# Solar.net
KiCad netlist of a schematic drawn in Altium Designer
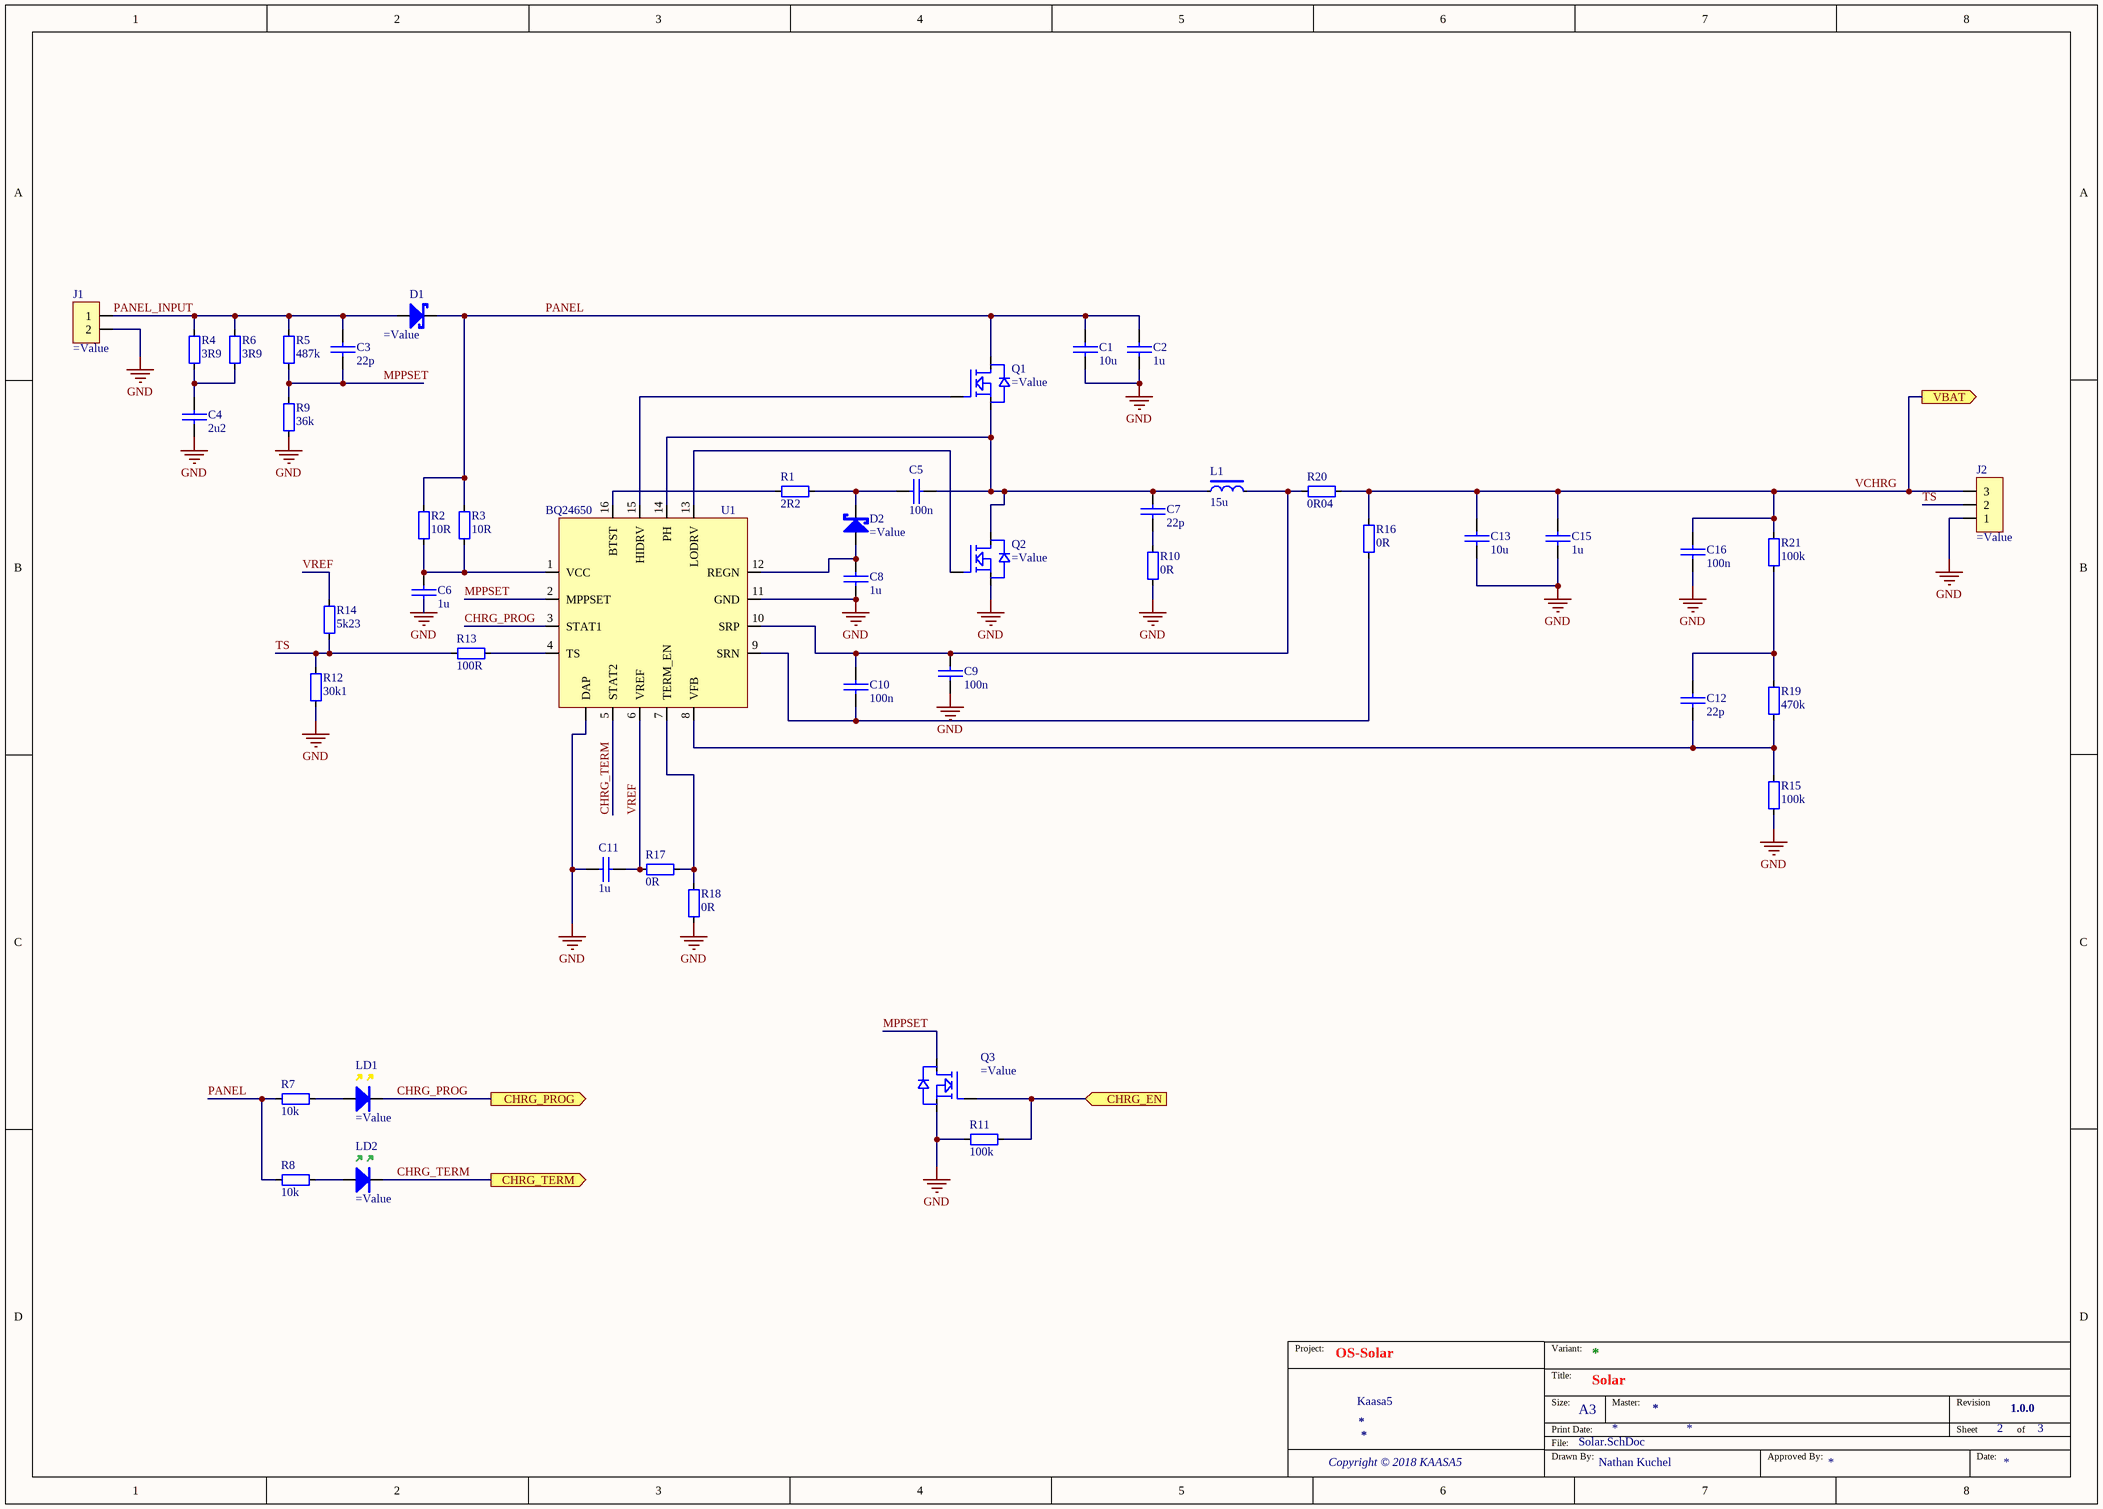
[diagram p0: Solar.SchDoc]

(export (version "E")
  (design (tool "Eeschema 10.0.6"))
  (components
    (comp (ref "C1")
      (value "10u")
      (footprint "CAPC3216X18N")
      (description "CAP SMD CER X7R 10% 50V 1206 (3216 Metric)")
      (fields
        (field (name "MANUFACTURER") "Samsung Electro-Mechanics")
        (field (name "PART NUMBER") "CL31B106KBHNNNE")
      )
      (libsource (lib "kaasa5") (part "C_NORM"))
    )
    (comp (ref "C2")
      (value "1u")
      (footprint "CAPC1608X09N")
      (description "CAP SMD CER X7R 10% 50V 0805 (2012 Metric)")
      (fields (field (name "MANUFACTURER") "Yageo") (field (name "PART NUMBER") "CC0805KKX7R9BB105"))
      (libsource (lib "kaasa5") (part "C_NORM"))
    )
    (comp (ref "C3")
      (value "22p")
      (footprint "CAPC1608X09N")
      (description "CAP SMD CER C0G/NPO 5% 50V 0603 (1608 Metric)")
      (fields (field (name "MANUFACTURER") "Yageo") (field (name "PART NUMBER") "CC0603JRNPO9BN220"))
      (libsource (lib "kaasa5") (part "C_NORM"))
    )
    (comp (ref "C4")
      (value "2u2")
      (footprint "CAPC2012X13N")
      (description "CAP SMD CER X7R 10% 35V 0805 (2012 Metric)")
      (fields (field (name "MANUFACTURER") "Taiyo Yuden") (field (name "PART NUMBER") "UMK212BB7225KG-T"))
      (libsource (lib "kaasa5") (part "C_NORM"))
    )
    (comp (ref "C5")
      (value "100n")
      (footprint "CAPC1608X09N")
      (description "CAP SMD CER X7R 10% 50V 0603 (1608 Metric)")
      (fields (field (name "MANUFACTURER") "Yageo") (field (name "PART NUMBER") "CC0603KRX7R9BB104"))
      (libsource (lib "kaasa5") (part "C_NORM"))
    )
    (comp (ref "C6")
      (value "1u")
      (footprint "CAPC1608X09N")
      (description "CAP SMD CER X7R 10% 25V 0603 (1608 Metric)")
      (fields (field (name "MANUFACTURER") "Yageo") (field (name "PART NUMBER") "CC0603KRX7R8BB105"))
      (libsource (lib "kaasa5") (part "C_NORM"))
    )
    (comp (ref "C7")
      (value "22p")
      (footprint "CAPC1608X09N")
      (description "CAP SMD CER C0G/NPO 5% 50V 0603 (1608 Metric)")
      (fields (field (name "MANUFACTURER") "Yageo") (field (name "PART NUMBER") "CC0603JRNPO9BN220"))
      (libsource (lib "kaasa5") (part "C_NORM"))
    )
    (comp (ref "C8")
      (value "1u")
      (footprint "CAPC1608X09N")
      (description "CAP SMD CER X7R 10% 25V 0603 (1608 Metric)")
      (fields (field (name "MANUFACTURER") "Yageo") (field (name "PART NUMBER") "CC0603KRX7R8BB105"))
      (libsource (lib "kaasa5") (part "C_NORM"))
    )
    (comp (ref "C9")
      (value "100n")
      (footprint "CAPC1608X09N")
      (description "CAP SMD CER X7R 10% 50V 0603 (1608 Metric)")
      (fields (field (name "MANUFACTURER") "Yageo") (field (name "PART NUMBER") "CC0603KRX7R9BB104"))
      (libsource (lib "kaasa5") (part "C_NORM"))
    )
    (comp (ref "C10")
      (value "100n")
      (footprint "CAPC1608X09N")
      (description "CAP SMD CER X7R 10% 50V 0603 (1608 Metric)")
      (fields (field (name "MANUFACTURER") "Yageo") (field (name "PART NUMBER") "CC0603KRX7R9BB104"))
      (libsource (lib "kaasa5") (part "C_NORM"))
    )
    (comp (ref "C11")
      (value "1u")
      (footprint "CAPC1608X09N")
      (description "CAP SMD CER X7R 10% 25V 0603 (1608 Metric)")
      (fields (field (name "MANUFACTURER") "Yageo") (field (name "PART NUMBER") "CC0603KRX7R8BB105"))
      (libsource (lib "kaasa5") (part "C_NORM"))
    )
    (comp (ref "C12")
      (value "22p")
      (footprint "CAPC1608X09N")
      (description "CAP SMD CER C0G/NPO 5% 50V 0603 (1608 Metric)")
      (fields (field (name "MANUFACTURER") "Yageo") (field (name "PART NUMBER") "CC0603JRNPO9BN220"))
      (libsource (lib "kaasa5") (part "C_NORM"))
    )
    (comp (ref "C13")
      (value "10u")
      (footprint "CAPC3216X18N")
      (description "CAP SMD CER X7R 10% 50V 1206 (3216 Metric)")
      (fields
        (field (name "MANUFACTURER") "Samsung Electro-Mechanics")
        (field (name "PART NUMBER") "CL31B106KBHNNNE")
      )
      (libsource (lib "kaasa5") (part "C_NORM"))
    )
    (comp (ref "C15")
      (value "1u")
      (footprint "CAPC1608X09N")
      (description "CAP SMD CER X7R 10% 25V 0603 (1608 Metric)")
      (fields (field (name "MANUFACTURER") "Yageo") (field (name "PART NUMBER") "CC0603KRX7R8BB105"))
      (libsource (lib "kaasa5") (part "C_NORM"))
    )
    (comp (ref "C16")
      (value "100n")
      (footprint "CAPC1608X09N")
      (description "CAP SMD CER X7R 10% 50V 0603 (1608 Metric)")
      (fields (field (name "MANUFACTURER") "Yageo") (field (name "PART NUMBER") "CC0603KRX7R9BB104"))
      (libsource (lib "kaasa5") (part "C_NORM"))
    )
    (comp (ref "D1")
      (value "~")
      (footprint "DIOSMCX25N")
      (description "DIODE SMD SCHOTTKY 40V 3A SMC")
      (fields (field (name "MANUFACTURER") "ON Semiconductor") (field (name "PART NUMBER") "MBRS340T3G"))
      (libsource (lib "") (part "D_SCHOTTKY_1"))
    )
    (comp (ref "D2")
      (value "~")
      (footprint "DIOSMBX25N")
      (description "DIODE SMD SCHOTTKY 40V 2A SMB")
      (fields (field (name "MANUFACTURER") "ON Semiconductor") (field (name "PART NUMBER") "MBRS240LT3G"))
      (libsource (lib "kaasa5") (part "D_SCHOTTKY"))
    )
    (comp (ref "J1")
      (value "~")
      (footprint "HDR1X2_350_RA")
      (description "CON THRU RIGHT ANGLE 8A 300V Header 1x2pin")
      (fields (field (name "MANUFACTURER") "Molex, LLC") (field (name "PART NUMBER") "0395021002"))
      (libsource (lib "kaasa5") (part "J_CON_SIL_2"))
    )
    (comp (ref "J2")
      (value "~")
      (footprint "HDR1X3_350_RA")
      (description "CON THRU RIGHT ANGLE 8A 300V Header 1x3pin")
      (fields (field (name "MANUFACTURER") "Molex, LLC") (field (name "PART NUMBER") "0395021003"))
      (libsource (lib "kaasa5") (part "J_CON_SIL_3"))
    )
    (comp (ref "L1")
      (value "15u")
      (footprint "INDP5050X28N")
      (description "IND SMD Shielded W/W 20% 1.37A 100mOhm 5028")
      (fields (field (name "MANUFACTURER") "Bourns Inc.") (field (name "PART NUMBER") "SRR5028-150Y"))
      (libsource (lib "kaasa5") (part "L_FER"))
    )
    (comp (ref "LD1")
      (value "~")
      (footprint "LEDC1608X06N-YELLOW")
      (description "LED SMD YELLOW 180mcd Max 0603 (1608 Metric)")
      (fields (field (name "MANUFACTURER") "Lite-On Inc.") (field (name "PART NUMBER") "LTST-C191KSKT"))
      (libsource (lib "kaasa5") (part "LED_NORM_YELLOW"))
    )
    (comp (ref "LD2")
      (value "~")
      (footprint "LEDC1608X06N-GREEN")
      (description "LED SMD GREEN 71mcd Max 0603 (1608 Metric)")
      (fields (field (name "MANUFACTURER") "Lite-On Inc.") (field (name "PART NUMBER") "LTST-C191KGKT"))
      (libsource (lib "kaasa5") (part "LED_NORM_GREEN"))
    )
    (comp (ref "Q1")
      (value "~")
      (footprint "SOT95P230X110-3N")
      (description "TRANS MOSFET N-Channel 30V 5.6A 32mOhm SOT23")
      (fields (field (name "MANUFACTURER") "Diodes Incorporated") (field (name "PART NUMBER") "DMN3042L-7"))
      (libsource (lib "kaasa5") (part "Q_MOSFET_N_E"))
    )
    (comp (ref "Q2")
      (value "~")
      (footprint "SOT95P230X110-3N")
      (description "TRANS MOSFET N-Channel 30V 5.6A 32mOhm SOT23")
      (fields (field (name "MANUFACTURER") "Diodes Incorporated") (field (name "PART NUMBER") "DMN3042L-7"))
      (libsource (lib "kaasa5") (part "Q_MOSFET_N_E"))
    )
    (comp (ref "Q3")
      (value "~")
      (footprint "SOT95P230X110-3N")
      (description "TRANS MOSFET N-Channel 60V 360mA SOT23")
      (fields (field (name "MANUFACTURER") "Nexperia USA Inc.") (field (name "PART NUMBER") "2N7002P,235"))
      (libsource (lib "kaasa5") (part "Q_MOSFET_N_E"))
    )
    (comp (ref "R1")
      (value "2R2")
      (footprint "RESC1608X06N")
      (description "RES SMD Think Film 1% 1/10W 150V 0603 (1608 Metric)")
      (fields (field (name "MANUFACTURER") "Yageo") (field (name "PART NUMBER") "RC0603FR-072R2L"))
      (libsource (lib "kaasa5") (part "R_NORM"))
    )
    (comp (ref "R2")
      (value "10R")
      (footprint "RESC1608X06N")
      (description "RES SMD Think Film 1% 1/10W 150V 0603 (1608 Metric)")
      (fields (field (name "MANUFACTURER") "Yageo") (field (name "PART NUMBER") "RC0603FR-0710RL"))
      (libsource (lib "kaasa5") (part "R_NORM"))
    )
    (comp (ref "R3")
      (value "10R")
      (footprint "RESC1608X06N")
      (description "RES SMD Think Film 1% 1/10W 150V 0603 (1608 Metric)")
      (fields (field (name "MANUFACTURER") "Yageo") (field (name "PART NUMBER") "RC0603FR-0710RL"))
      (libsource (lib "kaasa5") (part "R_NORM"))
    )
    (comp (ref "R4")
      (value "3R9")
      (footprint "RESC1608X06N")
      (description "RES SMD Think Film 1% 1/10W 150V 0603 (1608 Metric)")
      (fields (field (name "MANUFACTURER") "Yageo") (field (name "PART NUMBER") "RC0603FR-073R9L"))
      (libsource (lib "kaasa5") (part "R_NORM"))
    )
    (comp (ref "R5")
      (value "487k")
      (footprint "RESC1608X06N")
      (description "RES SMD Think Film 1% 1/10W 150V 0603 (1608 Metric)")
      (fields (field (name "MANUFACTURER") "Yageo") (field (name "PART NUMBER") "RC0603FR-07487KL"))
      (libsource (lib "kaasa5") (part "R_NORM"))
    )
    (comp (ref "R6")
      (value "3R9")
      (footprint "RESC1608X06N")
      (description "RES SMD Think Film 1% 1/10W 150V 0603 (1608 Metric)")
      (fields (field (name "MANUFACTURER") "Yageo") (field (name "PART NUMBER") "RC0603FR-073R9L"))
      (libsource (lib "kaasa5") (part "R_NORM"))
    )
    (comp (ref "R7")
      (value "10k")
      (footprint "RESC1608X06N")
      (description "RES SMD Think Film 1% 1/10W 150V 0603 (1608 Metric)")
      (fields (field (name "MANUFACTURER") "Yageo") (field (name "PART NUMBER") "RC0603FR-0710KL"))
      (libsource (lib "kaasa5") (part "R_NORM"))
    )
    (comp (ref "R8")
      (value "10k")
      (footprint "RESC1608X06N")
      (description "RES SMD Think Film 1% 1/10W 150V 0603 (1608 Metric)")
      (fields (field (name "MANUFACTURER") "Yageo") (field (name "PART NUMBER") "RC0603FR-0710KL"))
      (libsource (lib "kaasa5") (part "R_NORM"))
    )
    (comp (ref "R9")
      (value "36k")
      (footprint "RESC1608X06N")
      (description "RES SMD Think Film 1% 1/10W 150V 0603 (1608 Metric)")
      (fields (field (name "MANUFACTURER") "Yageo") (field (name "PART NUMBER") "RC0603FR-0736KL"))
      (libsource (lib "kaasa5") (part "R_NORM"))
    )
    (comp (ref "R10")
      (value "0R")
      (footprint "RESC1608X06N")
      (description "RES SMD Think Film 1% 1/10W 1A 0603 (1608 Metric)")
      (fields (field (name "MANUFACTURER") "Yageo") (field (name "PART NUMBER") "RC0603FR-070RL"))
      (libsource (lib "kaasa5") (part "R_NORM"))
    )
    (comp (ref "R11")
      (value "100k")
      (footprint "RESC1608X06N")
      (description "RES SMD Think Film 1% 1/10W 150V 0603 (1608 Metric)")
      (fields (field (name "MANUFACTURER") "Yageo") (field (name "PART NUMBER") "RC0603FR-07100KL"))
      (libsource (lib "kaasa5") (part "R_NORM"))
    )
    (comp (ref "R12")
      (value "30k1")
      (footprint "RESC1608X06N")
      (description "RES SMD Think Film 1% 1/10W 150V 0603 (1608 Metric)")
      (fields (field (name "MANUFACTURER") "Yageo") (field (name "PART NUMBER") "RC0603FR-0730K1L"))
      (libsource (lib "kaasa5") (part "R_NORM"))
    )
    (comp (ref "R13")
      (value "100R")
      (footprint "RESC1608X06N")
      (description "RES SMD Think Film 1% 1/10W 150V 0603 (1608 Metric)")
      (fields (field (name "MANUFACTURER") "Yageo") (field (name "PART NUMBER") "RC0603FR-07100RL"))
      (libsource (lib "kaasa5") (part "R_NORM"))
    )
    (comp (ref "R14")
      (value "5k23")
      (footprint "RESC1608X06N")
      (description "RES SMD Think Film 1% 1/10W 150V 0603 (1608 Metric)")
      (fields (field (name "MANUFACTURER") "Yageo") (field (name "PART NUMBER") "RC0603FR-075K23L"))
      (libsource (lib "kaasa5") (part "R_NORM"))
    )
    (comp (ref "R15")
      (value "100k")
      (footprint "RESC1608X06N")
      (description "RES SMD Think Film 1% 1/10W 150V 0603 (1608 Metric)")
      (fields (field (name "MANUFACTURER") "Yageo") (field (name "PART NUMBER") "RC0603FR-07100KL"))
      (libsource (lib "kaasa5") (part "R_NORM"))
    )
    (comp (ref "R16")
      (value "0R")
      (footprint "RESC1608X06N")
      (description "RES SMD Think Film 1% 1/10W 1A 0603 (1608 Metric)")
      (fields (field (name "MANUFACTURER") "Yageo") (field (name "PART NUMBER") "RC0603FR-070RL"))
      (libsource (lib "kaasa5") (part "R_NORM"))
    )
    (comp (ref "R17")
      (value "0R")
      (footprint "RESC1608X06N")
      (description "RES SMD Think Film 1% 1/10W 1A 0603 (1608 Metric)")
      (fields (field (name "MANUFACTURER") "Yageo") (field (name "PART NUMBER") "RC0603FR-070RL"))
      (libsource (lib "kaasa5") (part "R_NORM"))
    )
    (comp (ref "R18")
      (value "0R")
      (footprint "RESC1608X06N")
      (description "RES SMD Think Film 1% 1/10W 1A 0603 (1608 Metric)")
      (fields (field (name "MANUFACTURER") "Yageo") (field (name "PART NUMBER") "RC0603FR-070RL"))
      (libsource (lib "kaasa5") (part "R_NORM"))
    )
    (comp (ref "R19")
      (value "470k")
      (footprint "RESC1608X06N")
      (description "RES SMD Think Film 1% 1/10W 150V 0603 (1608 Metric)")
      (fields (field (name "MANUFACTURER") "Yageo") (field (name "PART NUMBER") "RC0603FR-07470KL"))
      (libsource (lib "kaasa5") (part "R_NORM"))
    )
    (comp (ref "R20")
      (value "0R04")
      (footprint "RESC3216X07N")
      (description "RES SMD Metal Strip 1% 1/2W 35ppm 1206 (3216 Metric)")
      (fields (field (name "MANUFACTURER") "Vishay Dale") (field (name "PART NUMBER") "WSK1206R0400FEA18"))
      (libsource (lib "kaasa5") (part "R_NORM"))
    )
    (comp (ref "R21")
      (value "100k")
      (footprint "RESC1608X06N")
      (description "RES SMD Think Film 1% 1/10W 150V 0603 (1608 Metric)")
      (fields (field (name "MANUFACTURER") "Yageo") (field (name "PART NUMBER") "RC0603FR-07100KL"))
      (libsource (lib "kaasa5") (part "R_NORM"))
    )
    (comp (ref "U1")
      (value "BQ24650")
      (footprint "QFN50P350X350X90-16N")
      (description "IC SMD SYNC SW-MODE BAT CHRGR MPPT 28V 600kHz QFN16")
      (fields (field (name "MANUFACTURER") "Texas Instruments") (field (name "PART NUMBER") "BQ24650RVAR"))
      (libsource (lib "kaasa5") (part "BQ24650"))
    )
  )
  (nets
    (net (code "1") (name "/CHRG_EN") (class "Default")
      (node (ref "Q3") (pin "1") (pinfunction "G_1") (pintype "passive"))
      (node (ref "R11") (pin "2") (pintype "passive"))
    )
    (net (code "2") (name "/CHRG_PROG") (class "Default")
      (node (ref "LD1") (pin "2") (pinfunction "K_2") (pintype "passive"))
      (node (ref "U1") (pin "3") (pinfunction "STAT1_3") (pintype "passive"))
    )
    (net (code "3") (name "/CHRG_TERM") (class "Default")
      (node (ref "LD2") (pin "2") (pinfunction "K_2") (pintype "passive"))
      (node (ref "U1") (pin "5") (pinfunction "STAT2_5") (pintype "passive"))
    )
    (net (code "4") (name "/MPPSET") (class "Default")
      (node (ref "C3") (pin "2") (pintype "passive"))
      (node (ref "Q3") (pin "3") (pinfunction "D_3") (pintype "passive"))
      (node (ref "R5") (pin "1") (pintype "passive"))
      (node (ref "R9") (pin "2") (pintype "passive"))
      (node (ref "U1") (pin "2") (pinfunction "MPPSET_2") (pintype "passive"))
    )
    (net (code "5") (name "/PANEL") (class "Default")
      (node (ref "C1") (pin "1") (pintype "passive"))
      (node (ref "C2") (pin "1") (pintype "passive"))
      (node (ref "D1") (pin "2") (pinfunction "K_2") (pintype "passive"))
      (node (ref "Q1") (pin "3") (pinfunction "D_3") (pintype "passive"))
      (node (ref "R2") (pin "2") (pintype "passive"))
      (node (ref "R3") (pin "2") (pintype "passive"))
      (node (ref "R7") (pin "1") (pintype "passive"))
      (node (ref "R8") (pin "1") (pintype "passive"))
    )
    (net (code "6") (name "/PANEL_INPUT") (class "Default")
      (node (ref "C3") (pin "1") (pintype "passive"))
      (node (ref "D1") (pin "1") (pinfunction "A_1") (pintype "passive"))
      (node (ref "J1") (pin "1") (pinfunction "1_1") (pintype "passive"))
      (node (ref "R4") (pin "2") (pintype "passive"))
      (node (ref "R5") (pin "2") (pintype "passive"))
      (node (ref "R6") (pin "2") (pintype "passive"))
    )
    (net (code "7") (name "/TS") (class "Default")
      (node (ref "J2") (pin "2") (pinfunction "2_2") (pintype "passive"))
      (node (ref "R12") (pin "2") (pintype "passive"))
      (node (ref "R13") (pin "1") (pintype "passive"))
      (node (ref "R14") (pin "1") (pintype "passive"))
    )
    (net (code "8") (name "/VCHRG") (class "Default")
      (node (ref "C13") (pin "1") (pintype "passive"))
      (node (ref "C15") (pin "1") (pintype "passive"))
      (node (ref "C16") (pin "1") (pintype "passive"))
      (node (ref "J2") (pin "3") (pinfunction "3_3") (pintype "passive"))
      (node (ref "R16") (pin "2") (pintype "passive"))
      (node (ref "R20") (pin "2") (pintype "passive"))
      (node (ref "R21") (pin "2") (pintype "passive"))
    )
    (net (code "9") (name "/VREF") (class "Default")
      (node (ref "C11") (pin "2") (pintype "passive"))
      (node (ref "R14") (pin "2") (pintype "passive"))
      (node (ref "R17") (pin "2") (pintype "passive"))
      (node (ref "U1") (pin "6") (pinfunction "VREF_6") (pintype "passive"))
    )
    (net (code "10") (name "GND") (class "Default")
      (node (ref "C1") (pin "2") (pintype "passive"))
      (node (ref "C11") (pin "1") (pintype "passive"))
      (node (ref "C13") (pin "2") (pintype "passive"))
      (node (ref "C15") (pin "2") (pintype "passive"))
      (node (ref "C16") (pin "2") (pintype "passive"))
      (node (ref "C2") (pin "2") (pintype "passive"))
      (node (ref "C4") (pin "2") (pintype "passive"))
      (node (ref "C6") (pin "2") (pintype "passive"))
      (node (ref "C8") (pin "2") (pintype "passive"))
      (node (ref "C9") (pin "2") (pintype "passive"))
      (node (ref "J1") (pin "2") (pinfunction "2_2") (pintype "passive"))
      (node (ref "J2") (pin "1") (pinfunction "1_1") (pintype "passive"))
      (node (ref "Q2") (pin "2") (pinfunction "S_2") (pintype "passive"))
      (node (ref "Q3") (pin "2") (pinfunction "S_2") (pintype "passive"))
      (node (ref "R10") (pin "1") (pintype "passive"))
      (node (ref "R11") (pin "1") (pintype "passive"))
      (node (ref "R12") (pin "1") (pintype "passive"))
      (node (ref "R15") (pin "1") (pintype "passive"))
      (node (ref "R18") (pin "1") (pintype "passive"))
      (node (ref "R9") (pin "1") (pintype "passive"))
      (node (ref "U1") (pin "11") (pinfunction "GND_11") (pintype "passive"))
      (node (ref "U1") (pin "DAP") (pinfunction "DAP_DAP") (pintype "passive"))
    )
    (net (code "11") (name "Net-(C4-Pad1)") (class "Default")
      (node (ref "C4") (pin "1") (pintype "passive"))
      (node (ref "R4") (pin "1") (pintype "passive"))
      (node (ref "R6") (pin "1") (pintype "passive"))
    )
    (net (code "12") (name "Net-(C7-Pad2)") (class "Default")
      (node (ref "C7") (pin "2") (pintype "passive"))
      (node (ref "R10") (pin "2") (pintype "passive"))
    )
    (net (code "13") (name "Net-(C12-Pad1)") (class "Default")
      (node (ref "C12") (pin "1") (pintype "passive"))
      (node (ref "R19") (pin "2") (pintype "passive"))
      (node (ref "R21") (pin "1") (pintype "passive"))
    )
    (net (code "14") (name "Net-(D2-A)") (class "Default")
      (node (ref "C8") (pin "1") (pintype "passive"))
      (node (ref "D2") (pin "1") (pinfunction "A_1") (pintype "passive"))
      (node (ref "U1") (pin "12") (pinfunction "REGN_12") (pintype "passive"))
    )
    (net (code "15") (name "Net-(D2-K)") (class "Default")
      (node (ref "C5") (pin "1") (pintype "passive"))
      (node (ref "D2") (pin "2") (pinfunction "K_2") (pintype "passive"))
      (node (ref "R1") (pin "2") (pintype "passive"))
    )
    (net (code "16") (name "Net-(LD1-A)") (class "Default")
      (node (ref "LD1") (pin "1") (pinfunction "A_1") (pintype "passive"))
      (node (ref "R7") (pin "2") (pintype "passive"))
    )
    (net (code "17") (name "Net-(LD2-A)") (class "Default")
      (node (ref "LD2") (pin "1") (pinfunction "A_1") (pintype "passive"))
      (node (ref "R8") (pin "2") (pintype "passive"))
    )
    (net (code "18") (name "Net-(Q1-G)") (class "Default")
      (node (ref "Q1") (pin "1") (pinfunction "G_1") (pintype "passive"))
      (node (ref "U1") (pin "15") (pinfunction "HIDRV_15") (pintype "passive"))
    )
    (net (code "19") (name "Net-(Q1-S)") (class "Default")
      (node (ref "C5") (pin "2") (pintype "passive"))
      (node (ref "C7") (pin "1") (pintype "passive"))
      (node (ref "L1") (pin "1") (pintype "passive"))
      (node (ref "Q1") (pin "2") (pinfunction "S_2") (pintype "passive"))
      (node (ref "Q2") (pin "3") (pinfunction "D_3") (pintype "passive"))
      (node (ref "U1") (pin "14") (pinfunction "PH_14") (pintype "passive"))
    )
    (net (code "20") (name "Net-(Q2-G)") (class "Default")
      (node (ref "Q2") (pin "1") (pinfunction "G_1") (pintype "passive"))
      (node (ref "U1") (pin "13") (pinfunction "LODRV_13") (pintype "passive"))
    )
    (net (code "21") (name "Net-(U1-BTST)") (class "Default")
      (node (ref "R1") (pin "1") (pintype "passive"))
      (node (ref "U1") (pin "16") (pinfunction "BTST_16") (pintype "passive"))
    )
    (net (code "22") (name "Net-(U1-SRN)") (class "Default")
      (node (ref "C10") (pin "2") (pintype "passive"))
      (node (ref "R16") (pin "1") (pintype "passive"))
      (node (ref "U1") (pin "9") (pinfunction "SRN_9") (pintype "passive"))
    )
    (net (code "23") (name "Net-(U1-SRP)") (class "Default")
      (node (ref "C10") (pin "1") (pintype "passive"))
      (node (ref "C9") (pin "1") (pintype "passive"))
      (node (ref "L1") (pin "2") (pintype "passive"))
      (node (ref "R20") (pin "1") (pintype "passive"))
      (node (ref "U1") (pin "10") (pinfunction "SRP_10") (pintype "passive"))
    )
    (net (code "24") (name "Net-(U1-TERM_EN)") (class "Default")
      (node (ref "R17") (pin "1") (pintype "passive"))
      (node (ref "R18") (pin "2") (pintype "passive"))
      (node (ref "U1") (pin "7") (pinfunction "TERM_EN_7") (pintype "passive"))
    )
    (net (code "25") (name "Net-(U1-TS)") (class "Default")
      (node (ref "R13") (pin "2") (pintype "passive"))
      (node (ref "U1") (pin "4") (pinfunction "TS_4") (pintype "passive"))
    )
    (net (code "26") (name "Net-(U1-VCC)") (class "Default")
      (node (ref "C6") (pin "1") (pintype "passive"))
      (node (ref "R2") (pin "1") (pintype "passive"))
      (node (ref "R3") (pin "1") (pintype "passive"))
      (node (ref "U1") (pin "1") (pinfunction "VCC_1") (pintype "passive"))
    )
    (net (code "27") (name "Net-(U1-VFB)") (class "Default")
      (node (ref "C12") (pin "2") (pintype "passive"))
      (node (ref "R15") (pin "2") (pintype "passive"))
      (node (ref "R19") (pin "1") (pintype "passive"))
      (node (ref "U1") (pin "8") (pinfunction "VFB_8") (pintype "passive"))
    )
  )
)
